# drvoutput1.net
KiCad netlist of a schematic drawn in Altium Designer
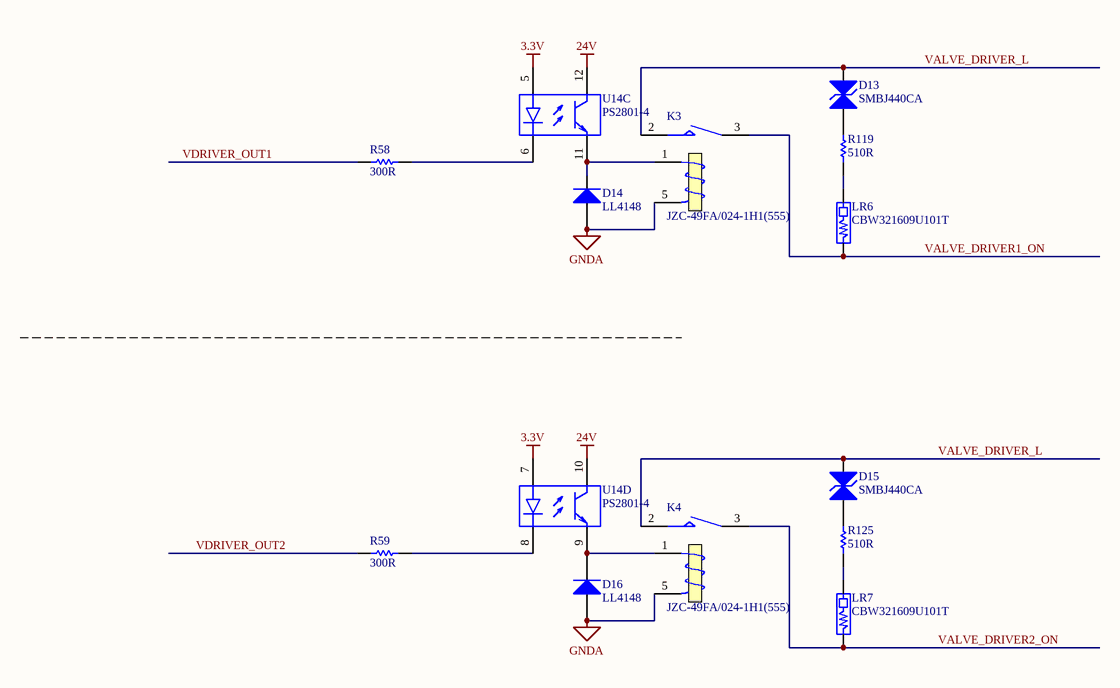
[diagram p0: drvoutput1.SchDoc]

(export (version "E")
  (design (tool "Eeschema 10.0.6"))
  (components
    (comp (ref "D13")
      (value "SMBJ440CA")
      (footprint "SMB")
      (description "Bi-dir TVS Diode")
      (fields (field (name "PUBLISHER") "Altium Limited"))
      (libsource (lib "UserLib") (part "Bi-dir TVS Diode"))
    )
    (comp (ref "D14")
      (value "LL4148")
      (footprint "CD2012-0805")
      (description "1 Amp General Purpose Rectifier")
      (fields (field (name "PUBLISHER") "Altium Limited"))
      (libsource (lib "Miscellaneous Devices") (part "Diode 1N4007"))
    )
    (comp (ref "D15")
      (value "SMBJ440CA")
      (footprint "SMB")
      (description "Bi-dir TVS Diode")
      (fields (field (name "PUBLISHER") "Altium Limited"))
      (libsource (lib "UserLib") (part "Bi-dir TVS Diode"))
    )
    (comp (ref "D16")
      (value "LL4148")
      (footprint "CD2012-0805")
      (description "1 Amp General Purpose Rectifier")
      (fields (field (name "PUBLISHER") "Altium Limited"))
      (libsource (lib "Miscellaneous Devices") (part "Diode 1N4007"))
    )
    (comp (ref "K3")
      (value "JZC-49FA/024-1H1(555)")
      (footprint "JZC-49FA")
      (description "Intermediate  Power  Relay")
      (fields (field (name "PUBLISHER") "Altium Limited"))
      (libsource (lib "UserSchDev") (part "JZC-49FA"))
    )
    (comp (ref "K4")
      (value "JZC-49FA/024-1H1(555)")
      (footprint "JZC-49FA")
      (description "Intermediate  Power  Relay")
      (fields (field (name "PUBLISHER") "Altium Limited"))
      (libsource (lib "UserSchDev") (part "JZC-49FA"))
    )
    (comp (ref "LR6")
      (value "CBW321609U101T")
      (footprint "INDC3216M")
      (description "EMI FILTERS,DC Resistance max.0.05~1.5 ohms,10 ~ 1000 ohms at 100MHz  Frequency")
      (libsource (lib "UserLib") (part "BLM10/11/21/31/41"))
    )
    (comp (ref "LR7")
      (value "CBW321609U101T")
      (footprint "INDC3216M")
      (description "EMI FILTERS,DC Resistance max.0.05~1.5 ohms,10 ~ 1000 ohms at 100MHz  Frequency")
      (libsource (lib "UserLib") (part "BLM10/11/21/31/41"))
    )
    (comp (ref "R58")
      (value "300R")
      (footprint "RESC2012M")
      (description "Resistor")
      (fields (field (name "PUBLISHER") "Altium Limited"))
      (libsource (lib "Miscellaneous Devices") (part "Res1"))
    )
    (comp (ref "R59")
      (value "300R")
      (footprint "RESC2012M")
      (description "Resistor")
      (fields (field (name "PUBLISHER") "Altium Limited"))
      (libsource (lib "Miscellaneous Devices") (part "Res1"))
    )
    (comp (ref "R119")
      (value "510R")
      (footprint "RESC3216M")
      (description "Metal film Resistor")
      (fields (field (name "PUBLISHER") "Altium Limited"))
      (libsource (lib "Miscellaneous Devices") (part "Res1"))
    )
    (comp (ref "R125")
      (value "510R")
      (footprint "RESC3216M")
      (description "Metal film Resistor")
      (fields (field (name "PUBLISHER") "Altium Limited"))
      (libsource (lib "Miscellaneous Devices") (part "Res1"))
    )
    (comp (ref "U14")
      (value "PS2801-4")
      (footprint "SOIC16_N")
      (fields (field (name "PUBLISHER") "Altium Limited"))
      (libsource (lib "UserSchDev") (part "PS2801-4"))
    )
  )
  (nets
    (net (code "1") (name "/VALVE_DRIVER1_ON") (class "Default")
      (node (ref "K3") (pin "3") (pinfunction "NO_3") (pintype "passive"))
      (node (ref "LR6") (pin "1") (pinfunction "1_1") (pintype "passive"))
    )
    (net (code "2") (name "/VALVE_DRIVER2_ON") (class "Default")
      (node (ref "K4") (pin "3") (pinfunction "NO_3") (pintype "passive"))
      (node (ref "LR7") (pin "1") (pinfunction "1_1") (pintype "passive"))
    )
    (net (code "3") (name "/VALVE_DRIVER_L") (class "Default")
      (node (ref "D13") (pin "2") (pinfunction "K_2") (pintype "passive"))
      (node (ref "D15") (pin "2") (pinfunction "K_2") (pintype "passive"))
      (node (ref "K3") (pin "2") (pinfunction "COM_2") (pintype "passive"))
      (node (ref "K4") (pin "2") (pinfunction "COM_2") (pintype "passive"))
    )
    (net (code "4") (name "/VDRIVER_OUT1") (class "Default")
      (node (ref "R58") (pin "1") (pinfunction "1_1") (pintype "passive"))
    )
    (net (code "5") (name "/VDRIVER_OUT2") (class "Default")
      (node (ref "R59") (pin "1") (pinfunction "1_1") (pintype "passive"))
    )
    (net (code "6") (name "3.3V") (class "Default")
      (node (ref "U14") (pin "5") (pinfunction "+_5") (pintype "passive"))
      (node (ref "U14") (pin "7") (pinfunction "+_7") (pintype "passive"))
    )
    (net (code "7") (name "24V") (class "Default")
      (node (ref "U14") (pin "10") (pinfunction "C_10") (pintype "passive"))
      (node (ref "U14") (pin "12") (pinfunction "C_12") (pintype "passive"))
    )
    (net (code "8") (name "GNDA") (class "Default")
      (node (ref "D14") (pin "1") (pinfunction "A_1") (pintype "passive"))
      (node (ref "D16") (pin "1") (pinfunction "A_1") (pintype "passive"))
      (node (ref "K3") (pin "5") (pinfunction "T2_5") (pintype "passive"))
      (node (ref "K4") (pin "5") (pinfunction "T2_5") (pintype "passive"))
    )
    (net (code "9") (name "Net-(D13-A)") (class "Default")
      (node (ref "D13") (pin "1") (pinfunction "A_1") (pintype "passive"))
      (node (ref "R119") (pin "2") (pinfunction "2_2") (pintype "passive"))
    )
    (net (code "10") (name "Net-(D14-K)") (class "Default")
      (node (ref "D14") (pin "2") (pinfunction "K_2") (pintype "passive"))
      (node (ref "K3") (pin "1") (pinfunction "1_1") (pintype "passive"))
      (node (ref "U14") (pin "11") (pinfunction "E_11") (pintype "passive"))
    )
    (net (code "11") (name "Net-(D15-A)") (class "Default")
      (node (ref "D15") (pin "1") (pinfunction "A_1") (pintype "passive"))
      (node (ref "R125") (pin "2") (pinfunction "2_2") (pintype "passive"))
    )
    (net (code "12") (name "Net-(D16-K)") (class "Default")
      (node (ref "D16") (pin "2") (pinfunction "K_2") (pintype "passive"))
      (node (ref "K4") (pin "1") (pinfunction "1_1") (pintype "passive"))
      (node (ref "U14") (pin "9") (pinfunction "E_9") (pintype "passive"))
    )
    (net (code "13") (name "Net-(LR6-Pad2)") (class "Default")
      (node (ref "LR6") (pin "2") (pinfunction "2_2") (pintype "passive"))
      (node (ref "R119") (pin "1") (pinfunction "1_1") (pintype "passive"))
    )
    (net (code "14") (name "Net-(LR7-Pad2)") (class "Default")
      (node (ref "LR7") (pin "2") (pinfunction "2_2") (pintype "passive"))
      (node (ref "R125") (pin "1") (pinfunction "1_1") (pintype "passive"))
    )
    (net (code "15") (name "Net-(U14C--)") (class "Default")
      (node (ref "R58") (pin "2") (pinfunction "2_2") (pintype "passive"))
      (node (ref "U14") (pin "6") (pinfunction "-_6") (pintype "passive"))
    )
    (net (code "16") (name "Net-(U14D--)") (class "Default")
      (node (ref "R59") (pin "2") (pinfunction "2_2") (pintype "passive"))
      (node (ref "U14") (pin "8") (pinfunction "-_8") (pintype "passive"))
    )
  )
)
